# Battery_Monitoring_with_kill.net
KiCad netlist of a schematic drawn in EAGLE
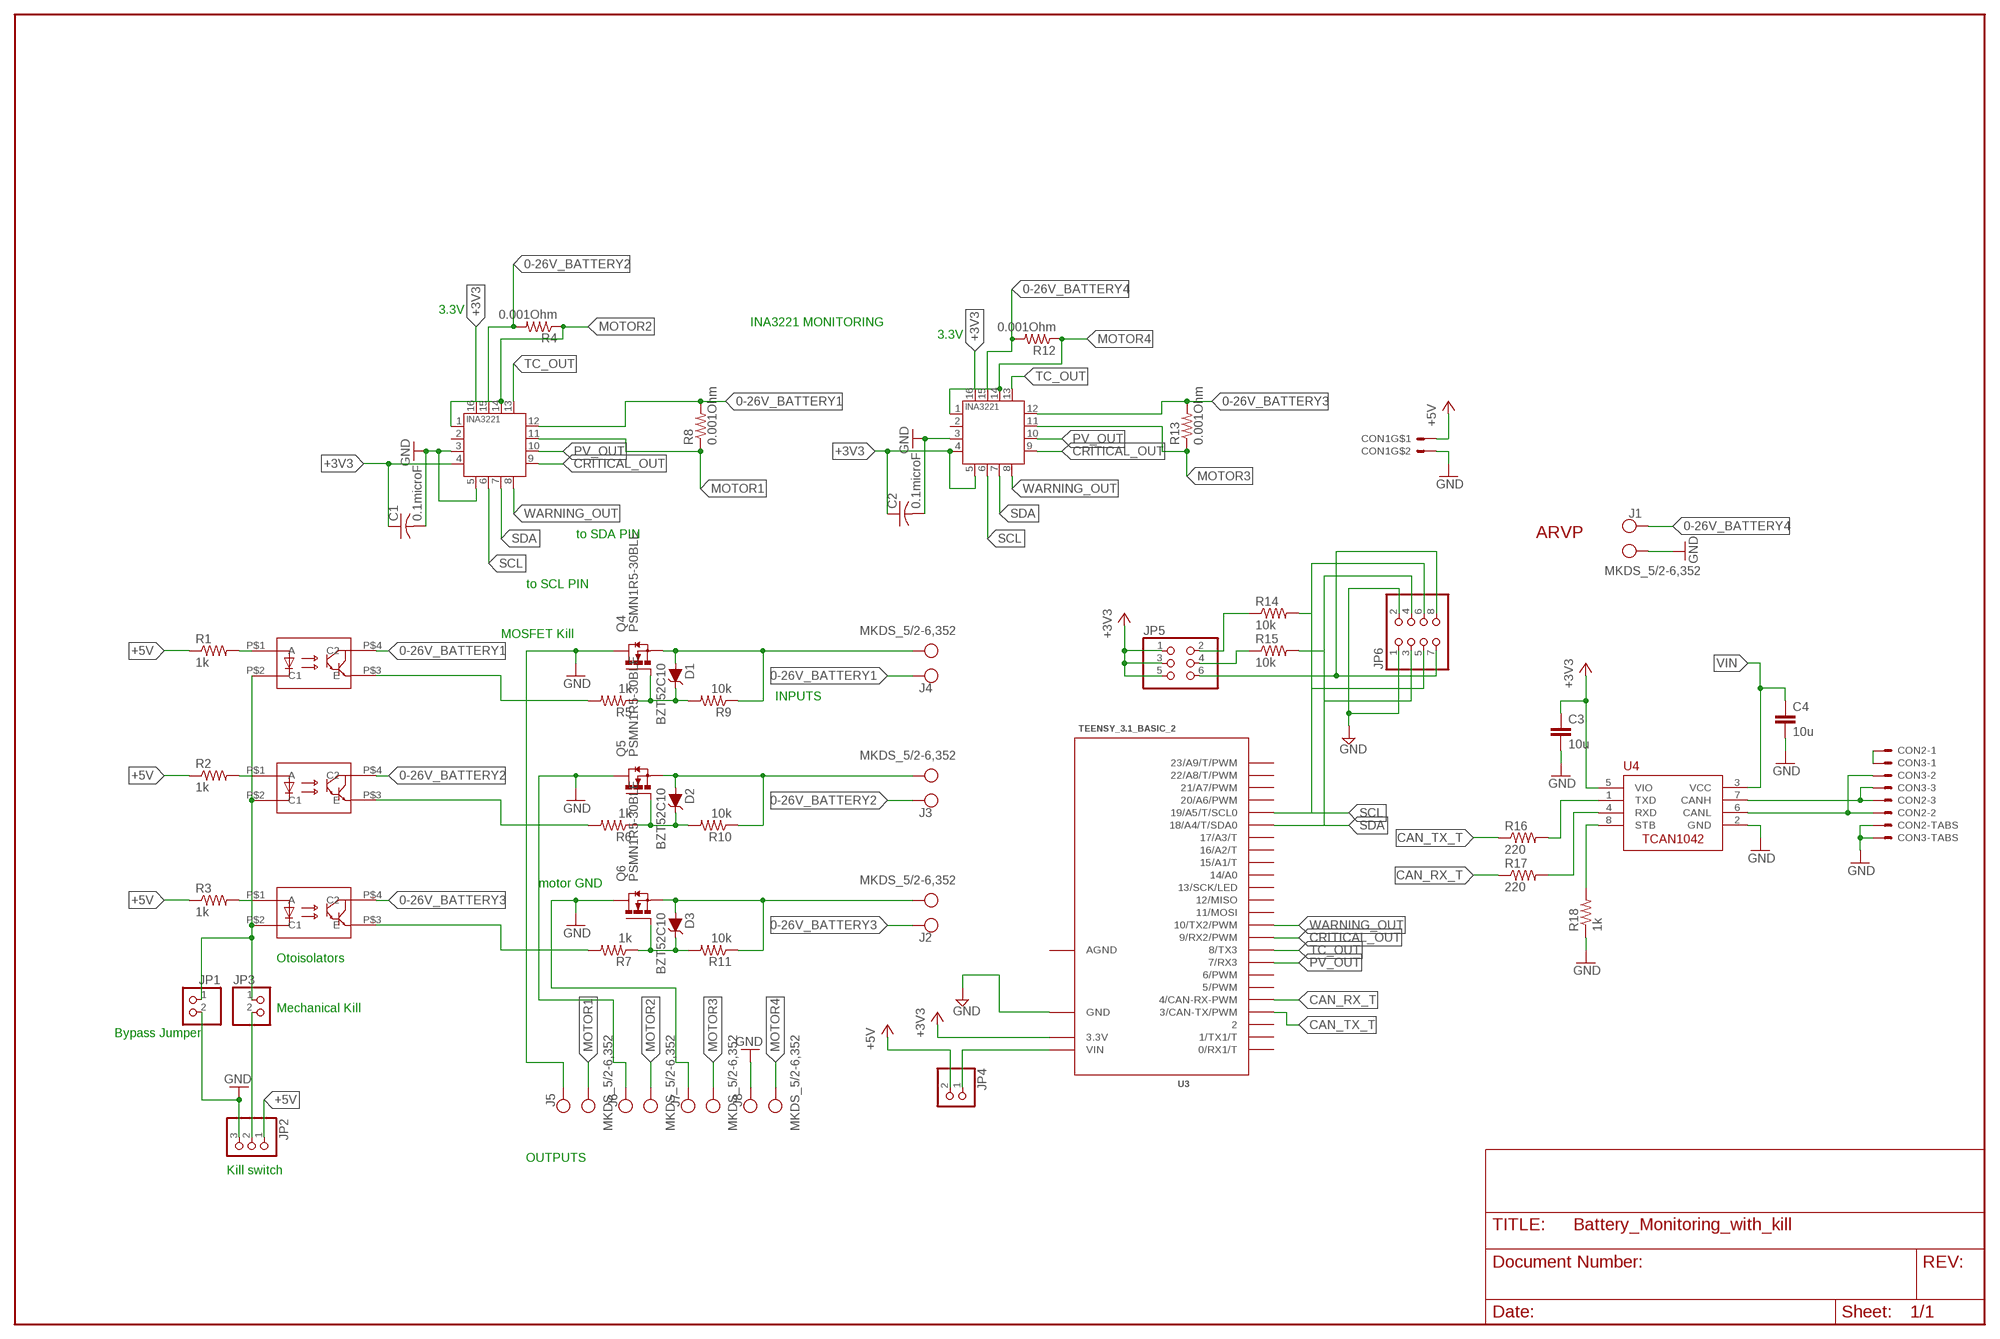
[diagram p0: schematic, sheet 1]

(export (version "E")
  (design (tool "Eeschema 10.0.6"))
  (components
    (comp (ref "ARVP1")
      (value "ARVP_LOGO")
      (footprint "eagle-import:ARVP")
      (libsource (lib "eagle-import") (part "ARVP_LOGO"))
    )
    (comp (ref "C1")
      (value "0.1microF")
      (footprint "eagle-import:C2012")
      (libsource (lib "eagle-import") (part "C-USC2012"))
    )
    (comp (ref "C2")
      (value "0.1microF")
      (footprint "eagle-import:C2012")
      (libsource (lib "eagle-import") (part "C-USC2012"))
    )
    (comp (ref "C3")
      (value "10u")
      (footprint "eagle-import:C0805")
      (libsource (lib "eagle-import") (part "C-EUC0805"))
    )
    (comp (ref "C4")
      (value "10u")
      (footprint "eagle-import:C0805")
      (libsource (lib "eagle-import") (part "C-EUC0805"))
    )
    (comp (ref "CON1")
      (value "MOLEX_5566-2")
      (footprint "eagle-import:5566-2")
      (libsource (lib "eagle-import") (part "MOLEX_5566-2"))
    )
    (comp (ref "CON2")
      (value "SM03B-GHS-TB")
      (footprint "eagle-import:SM03B-GHS-TB")
      (libsource (lib "eagle-import") (part "SM03B-GHS-TB"))
    )
    (comp (ref "CON3")
      (value "SM03B-GHS-TB")
      (footprint "eagle-import:SM03B-GHS-TB")
      (libsource (lib "eagle-import") (part "SM03B-GHS-TB"))
    )
    (comp (ref "D1")
      (value "BZT52C10")
      (footprint "eagle-import:SOD-123")
      (libsource (lib "eagle-import") (part "BZT52C10"))
    )
    (comp (ref "D2")
      (value "BZT52C10")
      (footprint "eagle-import:SOD-123")
      (libsource (lib "eagle-import") (part "BZT52C10"))
    )
    (comp (ref "D3")
      (value "BZT52C10")
      (footprint "eagle-import:SOD-123")
      (libsource (lib "eagle-import") (part "BZT52C10"))
    )
    (comp (ref "J1")
      (value "MKDS_5/2-6,352")
      (footprint "eagle-import:MKDS_5_2-6,35")
      (libsource (lib "eagle-import") (part "MKDS_5/2-6,352"))
    )
    (comp (ref "J2")
      (value "MKDS_5/2-6,352")
      (footprint "eagle-import:MKDS_5_2-6,35")
      (libsource (lib "eagle-import") (part "MKDS_5/2-6,352"))
    )
    (comp (ref "J3")
      (value "MKDS_5/2-6,352")
      (footprint "eagle-import:MKDS_5_2-6,35")
      (libsource (lib "eagle-import") (part "MKDS_5/2-6,352"))
    )
    (comp (ref "J4")
      (value "MKDS_5/2-6,352")
      (footprint "eagle-import:MKDS_5_2-6,35")
      (libsource (lib "eagle-import") (part "MKDS_5/2-6,352"))
    )
    (comp (ref "J5")
      (value "MKDS_5/2-6,352")
      (footprint "eagle-import:MKDS_5_2-6,35")
      (libsource (lib "eagle-import") (part "MKDS_5/2-6,352"))
    )
    (comp (ref "J6")
      (value "MKDS_5/2-6,352")
      (footprint "eagle-import:MKDS_5_2-6,35")
      (libsource (lib "eagle-import") (part "MKDS_5/2-6,352"))
    )
    (comp (ref "J7")
      (value "MKDS_5/2-6,352")
      (footprint "eagle-import:MKDS_5_2-6,35")
      (libsource (lib "eagle-import") (part "MKDS_5/2-6,352"))
    )
    (comp (ref "J8")
      (value "MKDS_5/2-6,352")
      (footprint "eagle-import:MKDS_5_2-6,35")
      (libsource (lib "eagle-import") (part "MKDS_5/2-6,352"))
    )
    (comp (ref "JP1")
      (value "PINHD-1X2")
      (footprint "eagle-import:1X02")
      (libsource (lib "eagle-import") (part "PINHD-1X2"))
    )
    (comp (ref "JP2")
      (value "PINHD-1X3")
      (footprint "eagle-import:1X03")
      (libsource (lib "eagle-import") (part "PINHD-1X3"))
    )
    (comp (ref "JP3")
      (value "PINHD-1X2")
      (footprint "eagle-import:1X02")
      (libsource (lib "eagle-import") (part "PINHD-1X2"))
    )
    (comp (ref "JP4")
      (value "PINHD-1X2")
      (footprint "eagle-import:1X02")
      (libsource (lib "eagle-import") (part "PINHD-1X2"))
    )
    (comp (ref "JP5")
      (value "PINHD-2X3")
      (footprint "eagle-import:2X03")
      (libsource (lib "eagle-import") (part "PINHD-2X3"))
    )
    (comp (ref "JP6")
      (value "PINHD-2X4")
      (footprint "eagle-import:2X04")
      (libsource (lib "eagle-import") (part "PINHD-2X4"))
    )
    (comp (ref "Q1")
      (value "TCLD1000CT")
      (footprint "eagle-import:SOP-4L")
      (fields (field (name "SPICEPREFIX") "E"))
      (libsource (lib "eagle-import") (part "TCLD1000CT"))
    )
    (comp (ref "Q2")
      (value "TCLD1000CT")
      (footprint "eagle-import:SOP-4L")
      (libsource (lib "eagle-import") (part "TCLD1000CT"))
    )
    (comp (ref "Q3")
      (value "TCLD1000CT")
      (footprint "eagle-import:SOP-4L")
      (libsource (lib "eagle-import") (part "TCLD1000CT"))
    )
    (comp (ref "Q4")
      (value "PSMN1R5-30BLE")
      (footprint "eagle-import:SOT404_D2PAK")
      (libsource (lib "eagle-import") (part "PSMN1R5-30BLE"))
    )
    (comp (ref "Q5")
      (value "PSMN1R5-30BLE")
      (footprint "eagle-import:SOT404_D2PAK")
      (libsource (lib "eagle-import") (part "PSMN1R5-30BLE"))
    )
    (comp (ref "Q6")
      (value "PSMN1R5-30BLE")
      (footprint "eagle-import:SOT404_D2PAK")
      (libsource (lib "eagle-import") (part "PSMN1R5-30BLE"))
    )
    (comp (ref "R1")
      (value "1k")
      (footprint "eagle-import:R0805")
      (libsource (lib "eagle-import") (part "R-US_R0805"))
    )
    (comp (ref "R2")
      (value "1k")
      (footprint "eagle-import:R0805")
      (libsource (lib "eagle-import") (part "R-US_R0805"))
    )
    (comp (ref "R3")
      (value "1k")
      (footprint "eagle-import:R0805")
      (libsource (lib "eagle-import") (part "R-US_R0805"))
    )
    (comp (ref "R4")
      (value "0.001Ohm")
      (footprint "eagle-import:3920")
      (libsource (lib "eagle-import") (part "HCS3920FT1L00"))
    )
    (comp (ref "R5")
      (value "1k")
      (footprint "eagle-import:M1206")
      (libsource (lib "eagle-import") (part "R-US_M1206"))
    )
    (comp (ref "R6")
      (value "1k")
      (footprint "eagle-import:M1206")
      (libsource (lib "eagle-import") (part "R-US_M1206"))
    )
    (comp (ref "R7")
      (value "1k")
      (footprint "eagle-import:M1206")
      (libsource (lib "eagle-import") (part "R-US_M1206"))
    )
    (comp (ref "R8")
      (value "0.001Ohm")
      (footprint "eagle-import:3920")
      (libsource (lib "eagle-import") (part "HCS3920FT1L00"))
    )
    (comp (ref "R9")
      (value "10k")
      (footprint "eagle-import:M1206")
      (libsource (lib "eagle-import") (part "R-US_M1206"))
    )
    (comp (ref "R10")
      (value "10k")
      (footprint "eagle-import:M1206")
      (libsource (lib "eagle-import") (part "R-US_M1206"))
    )
    (comp (ref "R11")
      (value "10k")
      (footprint "eagle-import:M1206")
      (libsource (lib "eagle-import") (part "R-US_M1206"))
    )
    (comp (ref "R12")
      (value "0.001Ohm")
      (footprint "eagle-import:3920")
      (libsource (lib "eagle-import") (part "HCS3920FT1L00"))
    )
    (comp (ref "R13")
      (value "0.001Ohm")
      (footprint "eagle-import:3920")
      (libsource (lib "eagle-import") (part "HCS3920FT1L00"))
    )
    (comp (ref "R14")
      (value "10k")
      (footprint "eagle-import:R1206")
      (libsource (lib "eagle-import") (part "rcl_334_R-US_R1206"))
    )
    (comp (ref "R15")
      (value "10k")
      (footprint "eagle-import:R1206")
      (libsource (lib "eagle-import") (part "rcl_334_R-US_R1206"))
    )
    (comp (ref "R16")
      (value "220")
      (footprint "eagle-import:R0805")
      (libsource (lib "eagle-import") (part "rcl_334_R-US_R0805"))
    )
    (comp (ref "R17")
      (value "220")
      (footprint "eagle-import:R0805")
      (libsource (lib "eagle-import") (part "rcl_334_R-US_R0805"))
    )
    (comp (ref "R18")
      (value "1k")
      (footprint "eagle-import:R0805")
      (libsource (lib "eagle-import") (part "rcl_334_R-US_R0805"))
    )
    (comp (ref "U1")
      (value "INA3221.")
      (footprint "eagle-import:HVQFN16_4X4")
      (libsource (lib "eagle-import") (part "INA3221."))
    )
    (comp (ref "U2")
      (value "INA3221.")
      (footprint "eagle-import:HVQFN16_4X4")
      (libsource (lib "eagle-import") (part "INA3221."))
    )
    (comp (ref "U3")
      (value "TEENSY_3.1_BASIC_2")
      (footprint "eagle-import:TEENSY_3.1_BASIC_2")
      (libsource (lib "eagle-import") (part "TEENSY_3.1_BASIC_2"))
    )
    (comp (ref "U4")
      (value "TCAN1042HVDR")
      (footprint "eagle-import:SO-8")
      (libsource (lib "eagle-import") (part "TCAN1042HVDR"))
    )
  )
  (nets
    (net (code "1") (name "+3V3") (class "Default")
      (node (ref "C1") (pin "1") (pinfunction "1_1") (pintype "passive"))
      (node (ref "C2") (pin "1") (pinfunction "1_1") (pintype "passive"))
      (node (ref "C3") (pin "1") (pinfunction "1_1") (pintype "passive"))
      (node (ref "JP5") (pin "1") (pinfunction "1_1") (pintype "passive"))
      (node (ref "JP5") (pin "3") (pinfunction "3_3") (pintype "passive"))
      (node (ref "JP5") (pin "5") (pinfunction "5_5") (pintype "passive"))
      (node (ref "U1") (pin "16") (pinfunction "VPU_16") (pintype "input"))
      (node (ref "U1") (pin "4") (pinfunction "VS_4") (pintype "power_in"))
      (node (ref "U2") (pin "16") (pinfunction "VPU_16") (pintype "input"))
      (node (ref "U2") (pin "4") (pinfunction "VS_4") (pintype "power_in"))
      (node (ref "U2") (pin "5") (pinfunction "A0_5") (pintype "input"))
      (node (ref "U3") (pin "3.3V") (pinfunction "3.3V_3.3V") (pintype "power_in"))
      (node (ref "U4") (pin "5") (pinfunction "VIO_5") (pintype "bidirectional"))
    )
    (net (code "2") (name "+5V") (class "Default")
      (node (ref "CON1") (pin "1") (pinfunction "S_1") (pintype "passive"))
      (node (ref "JP2") (pin "1") (pinfunction "1_1") (pintype "passive"))
      (node (ref "JP4") (pin "2") (pinfunction "2_2") (pintype "passive"))
      (node (ref "R1") (pin "1") (pinfunction "1_1") (pintype "passive"))
      (node (ref "R2") (pin "1") (pinfunction "1_1") (pintype "passive"))
      (node (ref "R3") (pin "1") (pinfunction "1_1") (pintype "passive"))
    )
    (net (code "3") (name "/AGND") (class "Default")
      (node (ref "U3") (pin "AGND") (pinfunction "AGND_AGND") (pintype "power_in"))
    )
    (net (code "4") (name "0-26V_BATTERY1") (class "Default")
      (node (ref "J4") (pin "2") (pinfunction "KL1_2") (pintype "passive"))
      (node (ref "Q1") (pin "P$4") (pinfunction "C2_P$4") (pintype "bidirectional"))
      (node (ref "R8") (pin "P$2") (pinfunction "2_P$2") (pintype "passive"))
      (node (ref "U1") (pin "12") (pinfunction "IN+1_12") (pintype "input"))
    )
    (net (code "5") (name "0-26V_BATTERY2") (class "Default")
      (node (ref "J3") (pin "2") (pinfunction "KL1_2") (pintype "passive"))
      (node (ref "Q2") (pin "P$4") (pinfunction "C2_P$4") (pintype "bidirectional"))
      (node (ref "R4") (pin "P$2") (pinfunction "2_P$2") (pintype "passive"))
      (node (ref "U1") (pin "15") (pinfunction "IN+2_15") (pintype "input"))
    )
    (net (code "6") (name "0-26V_BATTERY3") (class "Default")
      (node (ref "J2") (pin "2") (pinfunction "KL1_2") (pintype "passive"))
      (node (ref "Q3") (pin "P$4") (pinfunction "C2_P$4") (pintype "bidirectional"))
      (node (ref "R13") (pin "P$2") (pinfunction "2_P$2") (pintype "passive"))
      (node (ref "U2") (pin "12") (pinfunction "IN+1_12") (pintype "input"))
    )
    (net (code "7") (name "0-26V_BATTERY4") (class "Default")
      (node (ref "J1") (pin "2") (pinfunction "KL1_2") (pintype "passive"))
      (node (ref "R12") (pin "P$2") (pinfunction "2_P$2") (pintype "passive"))
      (node (ref "U2") (pin "15") (pinfunction "IN+2_15") (pintype "input"))
    )
    (net (code "8") (name "CAN_RX_T") (class "Default")
      (node (ref "R17") (pin "1") (pinfunction "1_1") (pintype "passive"))
      (node (ref "U3") (pin "4") (pinfunction "4/CAN-RX-PWM_4") (pintype "bidirectional"))
    )
    (net (code "9") (name "CAN_TX_T") (class "Default")
      (node (ref "R16") (pin "1") (pinfunction "1_1") (pintype "passive"))
      (node (ref "U3") (pin "3") (pinfunction "3/CAN-TX/PWM_3") (pintype "bidirectional"))
    )
    (net (code "10") (name "CRITICAL_OUT") (class "Default")
      (node (ref "U1") (pin "9") (pinfunction "CRITICAL_9") (pintype "output"))
      (node (ref "U2") (pin "9") (pinfunction "CRITICAL_9") (pintype "output"))
      (node (ref "U3") (pin "9") (pinfunction "9/RX2/PWM_9") (pintype "bidirectional"))
    )
    (net (code "11") (name "GND") (class "Default")
      (node (ref "C1") (pin "2") (pinfunction "2_2") (pintype "passive"))
      (node (ref "C2") (pin "2") (pinfunction "2_2") (pintype "passive"))
      (node (ref "C3") (pin "2") (pinfunction "2_2") (pintype "passive"))
      (node (ref "C4") (pin "2") (pinfunction "2_2") (pintype "passive"))
      (node (ref "CON1") (pin "2") (pinfunction "S_2") (pintype "passive"))
      (node (ref "CON2") (pin "P$4") (pinfunction "S_P$4") (pintype "passive"))
      (node (ref "CON2") (pin "P$5") (pinfunction "S_P$5") (pintype "passive"))
      (node (ref "CON3") (pin "P$4") (pinfunction "S_P$4") (pintype "passive"))
      (node (ref "CON3") (pin "P$5") (pinfunction "S_P$5") (pintype "passive"))
      (node (ref "J1") (pin "1") (pinfunction "KL_1") (pintype "passive"))
      (node (ref "J5") (pin "2") (pinfunction "KL1_2") (pintype "passive"))
      (node (ref "J6") (pin "2") (pinfunction "KL1_2") (pintype "passive"))
      (node (ref "J7") (pin "2") (pinfunction "KL1_2") (pintype "passive"))
      (node (ref "J8") (pin "2") (pinfunction "KL1_2") (pintype "passive"))
      (node (ref "JP1") (pin "2") (pinfunction "2_2") (pintype "passive"))
      (node (ref "JP2") (pin "3") (pinfunction "3_3") (pintype "passive"))
      (node (ref "JP6") (pin "1") (pinfunction "1_1") (pintype "passive"))
      (node (ref "JP6") (pin "2") (pinfunction "2_2") (pintype "passive"))
      (node (ref "Q4") (pin "2D") (pinfunction "D_2D") (pintype "passive"))
      (node (ref "Q5") (pin "2D") (pinfunction "D_2D") (pintype "passive"))
      (node (ref "Q6") (pin "2D") (pinfunction "D_2D") (pintype "passive"))
      (node (ref "R18") (pin "1") (pinfunction "1_1") (pintype "passive"))
      (node (ref "U1") (pin "3") (pinfunction "GND_3") (pintype "power_in"))
      (node (ref "U1") (pin "5") (pinfunction "A0_5") (pintype "input"))
      (node (ref "U2") (pin "3") (pinfunction "GND_3") (pintype "power_in"))
      (node (ref "U3") (pin "GND") (pinfunction "GND_GND") (pintype "power_in"))
      (node (ref "U4") (pin "2") (pinfunction "GND_2") (pintype "bidirectional"))
    )
    (net (code "12") (name "MOTOR1") (class "Default")
      (node (ref "J5") (pin "1") (pinfunction "KL_1") (pintype "passive"))
      (node (ref "R8") (pin "P$1") (pinfunction "1_P$1") (pintype "passive"))
      (node (ref "U1") (pin "11") (pinfunction "IN-1_11") (pintype "input"))
    )
    (net (code "13") (name "MOTOR2") (class "Default")
      (node (ref "J6") (pin "1") (pinfunction "KL_1") (pintype "passive"))
      (node (ref "R4") (pin "P$1") (pinfunction "1_P$1") (pintype "passive"))
      (node (ref "U1") (pin "1") (pinfunction "IN-3_1") (pintype "input"))
      (node (ref "U1") (pin "14") (pinfunction "IN-2_14") (pintype "input"))
    )
    (net (code "14") (name "MOTOR3") (class "Default")
      (node (ref "J7") (pin "1") (pinfunction "KL_1") (pintype "passive"))
      (node (ref "R13") (pin "P$1") (pinfunction "1_P$1") (pintype "passive"))
      (node (ref "U2") (pin "11") (pinfunction "IN-1_11") (pintype "input"))
    )
    (net (code "15") (name "MOTOR4") (class "Default")
      (node (ref "J8") (pin "1") (pinfunction "KL_1") (pintype "passive"))
      (node (ref "R12") (pin "P$1") (pinfunction "1_P$1") (pintype "passive"))
      (node (ref "U2") (pin "1") (pinfunction "IN-3_1") (pintype "input"))
      (node (ref "U2") (pin "14") (pinfunction "IN-2_14") (pintype "input"))
    )
    (net (code "16") (name "Net-(CON2A-S)") (class "Default")
      (node (ref "CON2") (pin "P$1") (pinfunction "S_P$1") (pintype "passive"))
      (node (ref "CON3") (pin "P$1") (pinfunction "S_P$1") (pintype "passive"))
    )
    (net (code "17") (name "Net-(CON2B-S)") (class "Default")
      (node (ref "CON2") (pin "P$2") (pinfunction "S_P$2") (pintype "passive"))
      (node (ref "CON3") (pin "P$2") (pinfunction "S_P$2") (pintype "passive"))
      (node (ref "U4") (pin "6") (pinfunction "CANL_6") (pintype "bidirectional"))
    )
    (net (code "18") (name "Net-(CON2C-S)") (class "Default")
      (node (ref "CON2") (pin "P$3") (pinfunction "S_P$3") (pintype "passive"))
      (node (ref "CON3") (pin "P$3") (pinfunction "S_P$3") (pintype "passive"))
      (node (ref "U4") (pin "7") (pinfunction "CANH_7") (pintype "bidirectional"))
    )
    (net (code "19") (name "Net-(D1-A)") (class "Default")
      (node (ref "D1") (pin "P$2") (pinfunction "A_P$2") (pintype "passive"))
      (node (ref "J4") (pin "1") (pinfunction "KL_1") (pintype "passive"))
      (node (ref "Q4") (pin "3S") (pinfunction "S_3S") (pintype "passive"))
      (node (ref "R9") (pin "1") (pinfunction "1_1") (pintype "passive"))
    )
    (net (code "20") (name "Net-(D1-C)") (class "Default")
      (node (ref "D1") (pin "P$1") (pinfunction "C_P$1") (pintype "passive"))
      (node (ref "Q4") (pin "1G") (pinfunction "G_1G") (pintype "passive"))
      (node (ref "R5") (pin "1") (pinfunction "1_1") (pintype "passive"))
      (node (ref "R9") (pin "2") (pinfunction "2_2") (pintype "passive"))
    )
    (net (code "21") (name "Net-(D2-A)") (class "Default")
      (node (ref "D2") (pin "P$2") (pinfunction "A_P$2") (pintype "passive"))
      (node (ref "J3") (pin "1") (pinfunction "KL_1") (pintype "passive"))
      (node (ref "Q5") (pin "3S") (pinfunction "S_3S") (pintype "passive"))
      (node (ref "R10") (pin "1") (pinfunction "1_1") (pintype "passive"))
    )
    (net (code "22") (name "Net-(D2-C)") (class "Default")
      (node (ref "D2") (pin "P$1") (pinfunction "C_P$1") (pintype "passive"))
      (node (ref "Q5") (pin "1G") (pinfunction "G_1G") (pintype "passive"))
      (node (ref "R10") (pin "2") (pinfunction "2_2") (pintype "passive"))
      (node (ref "R6") (pin "1") (pinfunction "1_1") (pintype "passive"))
    )
    (net (code "23") (name "Net-(D3-A)") (class "Default")
      (node (ref "D3") (pin "P$2") (pinfunction "A_P$2") (pintype "passive"))
      (node (ref "J2") (pin "1") (pinfunction "KL_1") (pintype "passive"))
      (node (ref "Q6") (pin "3S") (pinfunction "S_3S") (pintype "passive"))
      (node (ref "R11") (pin "1") (pinfunction "1_1") (pintype "passive"))
    )
    (net (code "24") (name "Net-(D3-C)") (class "Default")
      (node (ref "D3") (pin "P$1") (pinfunction "C_P$1") (pintype "passive"))
      (node (ref "Q6") (pin "1G") (pinfunction "G_1G") (pintype "passive"))
      (node (ref "R11") (pin "2") (pinfunction "2_2") (pintype "passive"))
      (node (ref "R7") (pin "1") (pinfunction "1_1") (pintype "passive"))
    )
    (net (code "25") (name "Net-(JP2-Pad2)") (class "Default")
      (node (ref "JP2") (pin "2") (pinfunction "2_2") (pintype "passive"))
      (node (ref "JP3") (pin "2") (pinfunction "2_2") (pintype "passive"))
    )
    (net (code "26") (name "Net-(JP5-Pad2)") (class "Default")
      (node (ref "JP5") (pin "2") (pinfunction "2_2") (pintype "passive"))
      (node (ref "R14") (pin "1") (pinfunction "1_1") (pintype "passive"))
    )
    (net (code "27") (name "Net-(JP5-Pad4)") (class "Default")
      (node (ref "JP5") (pin "4") (pinfunction "4_4") (pintype "passive"))
      (node (ref "R15") (pin "1") (pinfunction "1_1") (pintype "passive"))
    )
    (net (code "28") (name "Net-(JP5-Pad6)") (class "Default")
      (node (ref "JP5") (pin "6") (pinfunction "6_6") (pintype "passive"))
      (node (ref "JP6") (pin "7") (pinfunction "7_7") (pintype "passive"))
      (node (ref "JP6") (pin "8") (pinfunction "8_8") (pintype "passive"))
    )
    (net (code "29") (name "Net-(Q1-A)") (class "Default")
      (node (ref "Q1") (pin "P$1") (pinfunction "A_P$1") (pintype "bidirectional"))
      (node (ref "R1") (pin "2") (pinfunction "2_2") (pintype "passive"))
    )
    (net (code "30") (name "Net-(Q1-C1)") (class "Default")
      (node (ref "JP1") (pin "1") (pinfunction "1_1") (pintype "passive"))
      (node (ref "JP3") (pin "1") (pinfunction "1_1") (pintype "passive"))
      (node (ref "Q1") (pin "P$2") (pinfunction "C1_P$2") (pintype "bidirectional"))
      (node (ref "Q2") (pin "P$2") (pinfunction "C1_P$2") (pintype "bidirectional"))
      (node (ref "Q3") (pin "P$2") (pinfunction "C1_P$2") (pintype "bidirectional"))
    )
    (net (code "31") (name "Net-(Q1-E)") (class "Default")
      (node (ref "Q1") (pin "P$3") (pinfunction "E_P$3") (pintype "bidirectional"))
      (node (ref "R5") (pin "2") (pinfunction "2_2") (pintype "passive"))
    )
    (net (code "32") (name "Net-(Q2-A)") (class "Default")
      (node (ref "Q2") (pin "P$1") (pinfunction "A_P$1") (pintype "bidirectional"))
      (node (ref "R2") (pin "2") (pinfunction "2_2") (pintype "passive"))
    )
    (net (code "33") (name "Net-(Q2-E)") (class "Default")
      (node (ref "Q2") (pin "P$3") (pinfunction "E_P$3") (pintype "bidirectional"))
      (node (ref "R6") (pin "2") (pinfunction "2_2") (pintype "passive"))
    )
    (net (code "34") (name "Net-(Q3-A)") (class "Default")
      (node (ref "Q3") (pin "P$1") (pinfunction "A_P$1") (pintype "bidirectional"))
      (node (ref "R3") (pin "2") (pinfunction "2_2") (pintype "passive"))
    )
    (net (code "35") (name "Net-(Q3-E)") (class "Default")
      (node (ref "Q3") (pin "P$3") (pinfunction "E_P$3") (pintype "bidirectional"))
      (node (ref "R7") (pin "2") (pinfunction "2_2") (pintype "passive"))
    )
    (net (code "36") (name "Net-(U4-RXD)") (class "Default")
      (node (ref "R17") (pin "2") (pinfunction "2_2") (pintype "passive"))
      (node (ref "U4") (pin "4") (pinfunction "RXD_4") (pintype "bidirectional"))
    )
    (net (code "37") (name "Net-(U4-STB)") (class "Default")
      (node (ref "R18") (pin "2") (pinfunction "2_2") (pintype "passive"))
      (node (ref "U4") (pin "8") (pinfunction "STB_8") (pintype "bidirectional"))
    )
    (net (code "38") (name "Net-(U4-TXD)") (class "Default")
      (node (ref "R16") (pin "2") (pinfunction "2_2") (pintype "passive"))
      (node (ref "U4") (pin "1") (pinfunction "TXD_1") (pintype "bidirectional"))
    )
    (net (code "39") (name "PV_OUT") (class "Default")
      (node (ref "U1") (pin "10") (pinfunction "PV_10") (pintype "output"))
      (node (ref "U2") (pin "10") (pinfunction "PV_10") (pintype "output"))
      (node (ref "U3") (pin "7") (pinfunction "7/RX3_7") (pintype "bidirectional"))
    )
    (net (code "40") (name "SCL") (class "Default")
      (node (ref "JP6") (pin "5") (pinfunction "5_5") (pintype "passive"))
      (node (ref "JP6") (pin "6") (pinfunction "6_6") (pintype "passive"))
      (node (ref "R14") (pin "2") (pinfunction "2_2") (pintype "passive"))
      (node (ref "U1") (pin "6") (pinfunction "SCL_6") (pintype "input"))
      (node (ref "U2") (pin "6") (pinfunction "SCL_6") (pintype "input"))
      (node (ref "U3") (pin "19/A5") (pinfunction "19/A5/T/SCL0_19/A5") (pintype "bidirectional"))
    )
    (net (code "41") (name "SDA") (class "Default")
      (node (ref "JP6") (pin "3") (pinfunction "3_3") (pintype "passive"))
      (node (ref "JP6") (pin "4") (pinfunction "4_4") (pintype "passive"))
      (node (ref "R15") (pin "2") (pinfunction "2_2") (pintype "passive"))
      (node (ref "U1") (pin "7") (pinfunction "SDA_7") (pintype "bidirectional"))
      (node (ref "U2") (pin "7") (pinfunction "SDA_7") (pintype "bidirectional"))
      (node (ref "U3") (pin "18/A4") (pinfunction "18/A4/T/SDA0_18/A4") (pintype "bidirectional"))
    )
    (net (code "42") (name "TC_OUT") (class "Default")
      (node (ref "U1") (pin "13") (pinfunction "TC_13") (pintype "output"))
      (node (ref "U2") (pin "13") (pinfunction "TC_13") (pintype "output"))
      (node (ref "U3") (pin "8") (pinfunction "8/TX3_8") (pintype "bidirectional"))
    )
    (net (code "43") (name "VIN") (class "Default")
      (node (ref "C4") (pin "1") (pinfunction "1_1") (pintype "passive"))
      (node (ref "JP4") (pin "1") (pinfunction "1_1") (pintype "passive"))
      (node (ref "U3") (pin "VIN") (pinfunction "VIN_VIN") (pintype "power_in"))
      (node (ref "U4") (pin "3") (pinfunction "VCC_3") (pintype "bidirectional"))
    )
    (net (code "44") (name "WARNING_OUT") (class "Default")
      (node (ref "U1") (pin "8") (pinfunction "WARNING_8") (pintype "output"))
      (node (ref "U2") (pin "8") (pinfunction "WARNING_8") (pintype "output"))
      (node (ref "U3") (pin "10") (pinfunction "10/TX2/PWM_10") (pintype "bidirectional"))
    )
    (net (code "45") (name "unconnected-(U1-IN+3-Pad2)") (class "Default")
      (node (ref "U1") (pin "2") (pinfunction "IN+3_2") (pintype "input"))
    )
    (net (code "46") (name "unconnected-(U2-IN+3-Pad2)") (class "Default")
      (node (ref "U2") (pin "2") (pinfunction "IN+3_2") (pintype "input"))
    )
    (net (code "47") (name "unconnected-(U3-0{slash}RX1{slash}T-Pad0)") (class "Default")
      (node (ref "U3") (pin "0") (pinfunction "0/RX1/T_0") (pintype "bidirectional"))
    )
    (net (code "48") (name "unconnected-(U3-1{slash}TX1{slash}T-Pad1)") (class "Default")
      (node (ref "U3") (pin "1") (pinfunction "1/TX1/T_1") (pintype "bidirectional"))
    )
    (net (code "49") (name "unconnected-(U3-5{slash}PWM-Pad5)") (class "Default")
      (node (ref "U3") (pin "5") (pinfunction "5/PWM_5") (pintype "bidirectional"))
    )
    (net (code "50") (name "unconnected-(U3-6{slash}PWM-Pad6)") (class "Default")
      (node (ref "U3") (pin "6") (pinfunction "6/PWM_6") (pintype "bidirectional"))
    )
    (net (code "51") (name "unconnected-(U3-11{slash}MOSI-Pad11)") (class "Default")
      (node (ref "U3") (pin "11") (pinfunction "11/MOSI_11") (pintype "bidirectional"))
    )
    (net (code "52") (name "unconnected-(U3-12{slash}MISO-Pad12)") (class "Default")
      (node (ref "U3") (pin "12") (pinfunction "12/MISO_12") (pintype "bidirectional"))
    )
    (net (code "53") (name "unconnected-(U3-13{slash}SCK{slash}LED-Pad13)") (class "Default")
      (node (ref "U3") (pin "13") (pinfunction "13/SCK/LED_13") (pintype "bidirectional"))
    )
    (net (code "54") (name "unconnected-(U3-15{slash}A1{slash}T-Pad15{slash}A1)") (class "Default")
      (node (ref "U3") (pin "15/A1") (pinfunction "15/A1/T_15/A1") (pintype "bidirectional"))
    )
    (net (code "55") (name "unconnected-(U3-16{slash}A2{slash}T-Pad16{slash}A2)") (class "Default")
      (node (ref "U3") (pin "16/A2") (pinfunction "16/A2/T_16/A2") (pintype "bidirectional"))
    )
    (net (code "56") (name "unconnected-(U3-17{slash}A3{slash}T-Pad17{slash}A3)") (class "Default")
      (node (ref "U3") (pin "17/A3") (pinfunction "17/A3/T_17/A3") (pintype "bidirectional"))
    )
    (net (code "57") (name "unconnected-(U3-20{slash}A6{slash}PWM-Pad20{slash}A6)") (class "Default")
      (node (ref "U3") (pin "20/A6") (pinfunction "20/A6/PWM_20/A6") (pintype "bidirectional"))
    )
    (net (code "58") (name "unconnected-(U3-21{slash}A7{slash}PWM-Pad21{slash}A7)") (class "Default")
      (node (ref "U3") (pin "21/A7") (pinfunction "21/A7/PWM_21/A7") (pintype "bidirectional"))
    )
    (net (code "59") (name "unconnected-(U3-22{slash}A8{slash}T{slash}PWM-Pad22{slash}A8)") (class "Default")
      (node (ref "U3") (pin "22/A8") (pinfunction "22/A8/T/PWM_22/A8") (pintype "bidirectional"))
    )
    (net (code "60") (name "unconnected-(U3-23{slash}A9{slash}T{slash}PWM-Pad23{slash}A9)") (class "Default")
      (node (ref "U3") (pin "23/A9") (pinfunction "23/A9/T/PWM_23/A9") (pintype "bidirectional"))
    )
    (net (code "61") (name "unconnected-(U3-Pad2)") (class "Default")
      (node (ref "U3") (pin "2") (pinfunction "2_2") (pintype "bidirectional"))
    )
    (net (code "62") (name "unconnected-(U3-Pad14{slash}A0)") (class "Default")
      (node (ref "U3") (pin "14/A0") (pinfunction "14/A0_14/A0") (pintype "bidirectional"))
    )
  )
)
